# Project.net
KiCad netlist of a schematic drawn in EAGLE
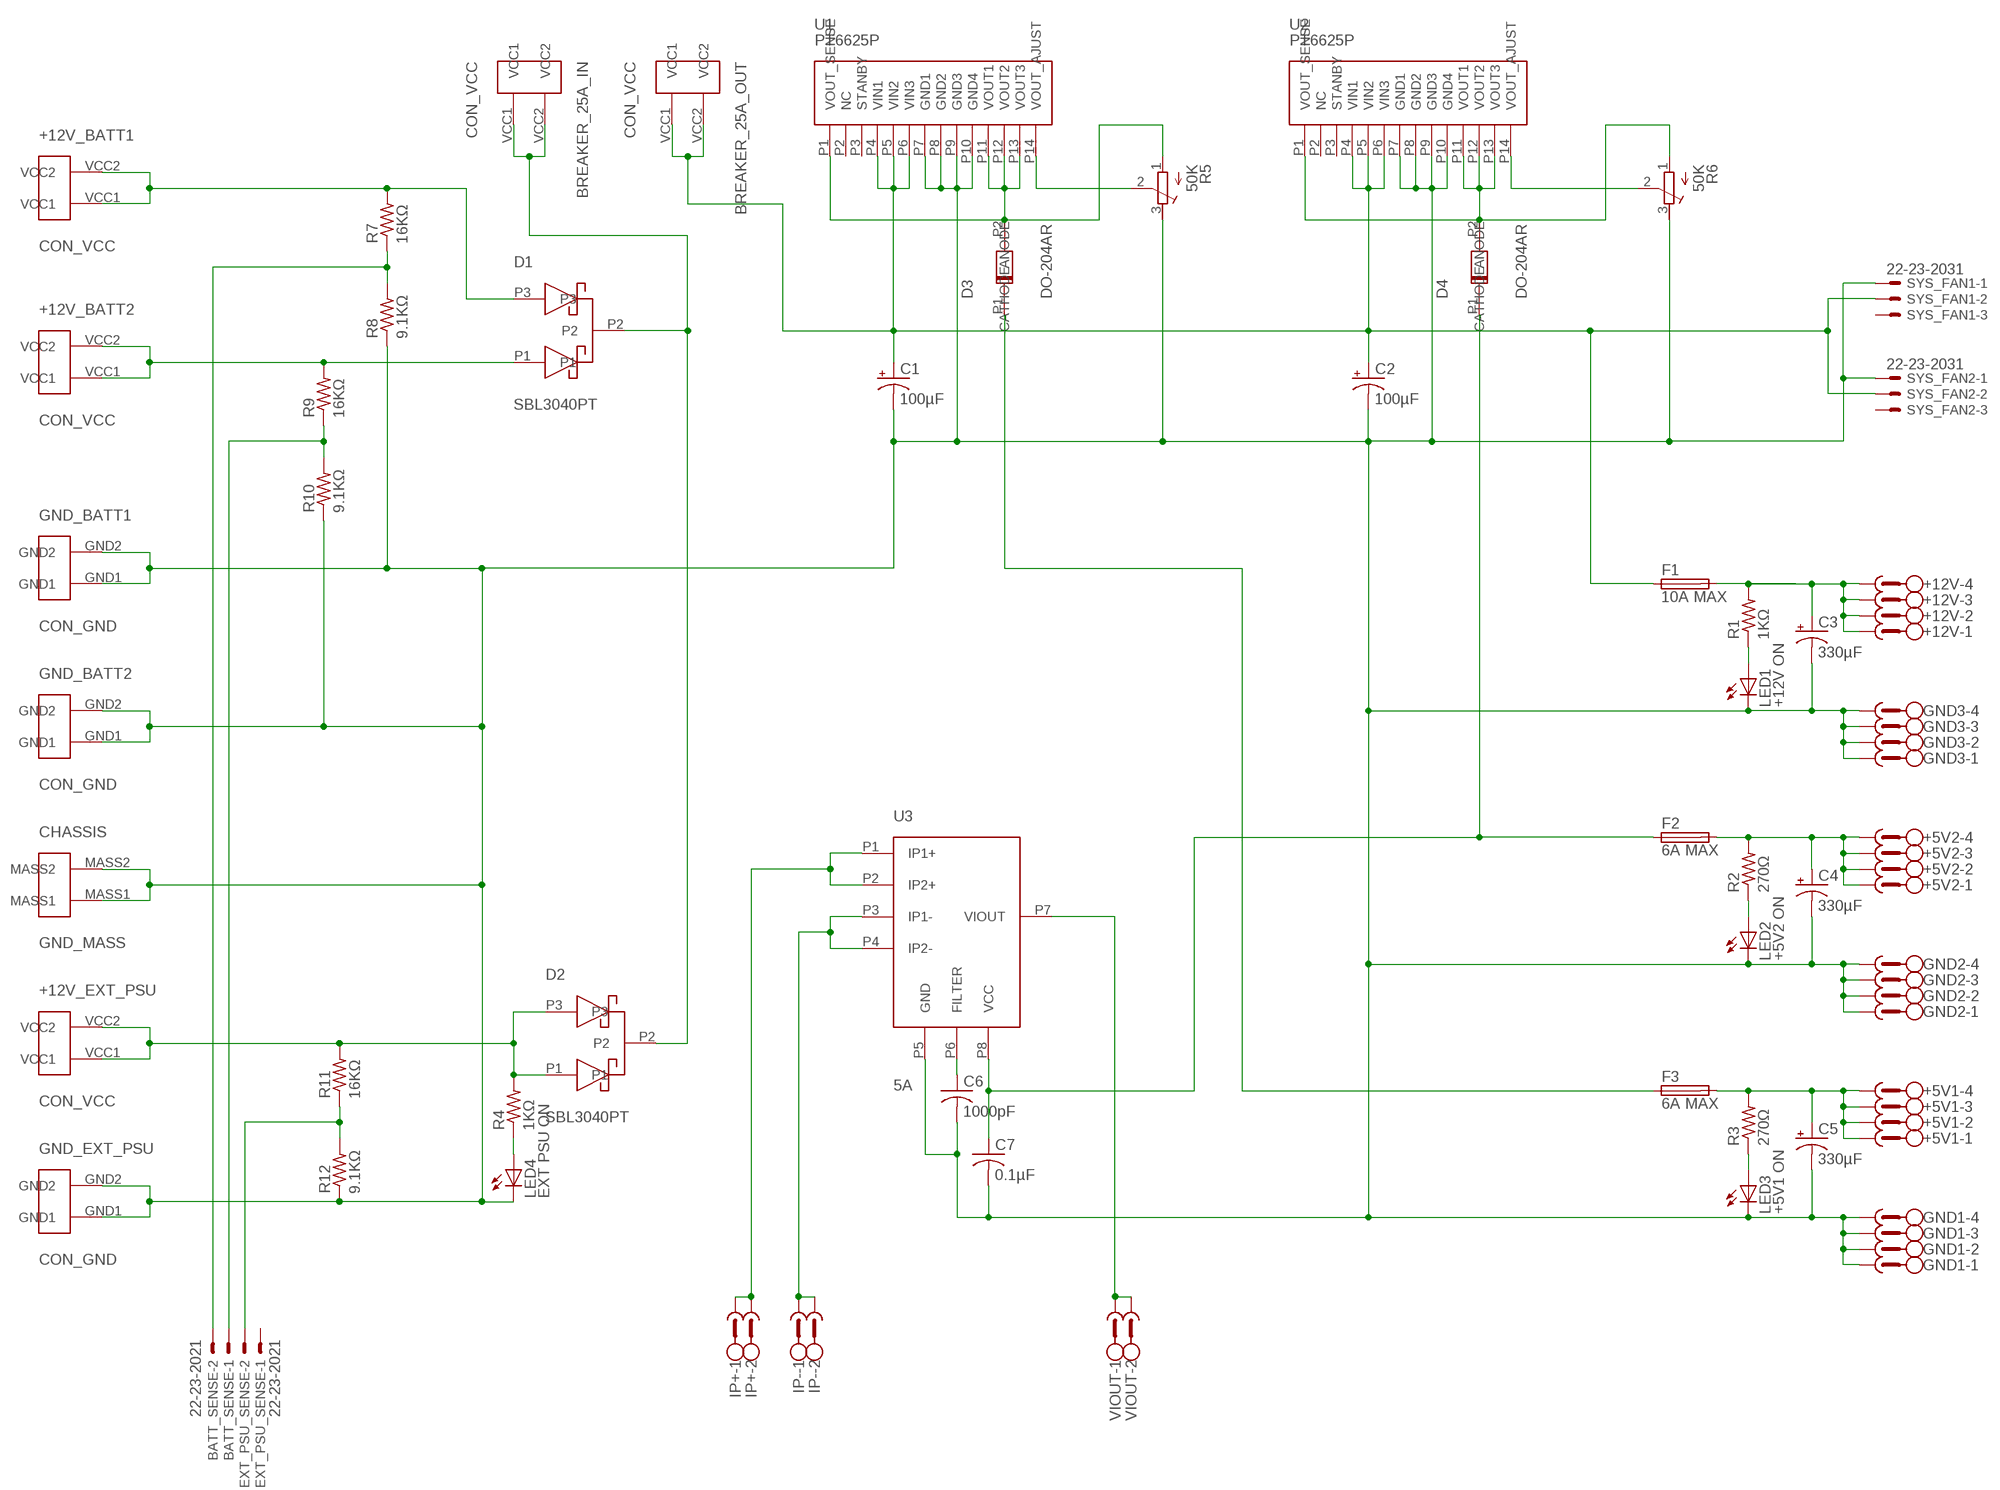
[diagram p0: schematic, sheet 1]

(export (version "E")
  (design (tool "Eeschema 10.0.6"))
  (components
    (comp (ref "+5V1")
      (value "MC1.5/4-G-3.81")
      (footprint "eagle-import:MC1.5_4-G-3.81")
      (libsource (lib "eagle-import") (part "MC1.5/4-G-3.81"))
    )
    (comp (ref "+5V2")
      (value "MC1.5/4-G-3.81")
      (footprint "eagle-import:MC1.5_4-G-3.81")
      (libsource (lib "eagle-import") (part "MC1.5/4-G-3.81"))
    )
    (comp (ref "+12V")
      (value "MC1.5/4-G-3.81")
      (footprint "eagle-import:MC1.5_4-G-3.81")
      (libsource (lib "eagle-import") (part "MC1.5/4-G-3.81"))
    )
    (comp (ref "+12V_BATT1")
      (value "CON_VCC")
      (footprint "eagle-import:CON_VCC")
      (libsource (lib "eagle-import") (part "CON_VCC"))
    )
    (comp (ref "+12V_BATT2")
      (value "CON_VCC")
      (footprint "eagle-import:CON_VCC")
      (libsource (lib "eagle-import") (part "CON_VCC"))
    )
    (comp (ref "+12V_EXT_PSU")
      (value "CON_VCC")
      (footprint "eagle-import:CON_VCC")
      (libsource (lib "eagle-import") (part "CON_VCC"))
    )
    (comp (ref "BATT_SENSE")
      (value "22-23-2021")
      (footprint "eagle-import:22-23-2021")
      (fields (field (name "MF") "MOLEX"))
      (libsource (lib "eagle-import") (part "22-23-2021"))
    )
    (comp (ref "BREAKER_25A_IN")
      (value "CON_VCC")
      (footprint "eagle-import:CON_VCC")
      (libsource (lib "eagle-import") (part "CON_VCC"))
    )
    (comp (ref "BREAKER_25A_OUT")
      (value "CON_VCC")
      (footprint "eagle-import:CON_VCC")
      (libsource (lib "eagle-import") (part "CON_VCC"))
    )
    (comp (ref "C1")
      (value "100µF")
      (footprint "eagle-import:E2,5-6")
      (libsource (lib "eagle-import") (part "CPOL-USE2.5-6"))
    )
    (comp (ref "C2")
      (value "100µF")
      (footprint "eagle-import:E2,5-6")
      (libsource (lib "eagle-import") (part "CPOL-USE2.5-6"))
    )
    (comp (ref "C3")
      (value "330µF")
      (footprint "eagle-import:E5-10,5")
      (libsource (lib "eagle-import") (part "CPOL-USE5-10.5"))
    )
    (comp (ref "C4")
      (value "330µF")
      (footprint "eagle-import:E5-10,5")
      (libsource (lib "eagle-import") (part "CPOL-USE5-10.5"))
    )
    (comp (ref "C5")
      (value "330µF")
      (footprint "eagle-import:E5-10,5")
      (libsource (lib "eagle-import") (part "CPOL-USE5-10.5"))
    )
    (comp (ref "C6")
      (value "1000pF")
      (footprint "eagle-import:C0805")
      (libsource (lib "eagle-import") (part "C-USC0805"))
    )
    (comp (ref "C7")
      (value "0.1µF")
      (footprint "eagle-import:C0805")
      (libsource (lib "eagle-import") (part "C-USC0805"))
    )
    (comp (ref "CHASSIS")
      (value "GND_MASS")
      (footprint "eagle-import:CON_MASS")
      (libsource (lib "eagle-import") (part "GND_MASS"))
    )
    (comp (ref "D1")
      (value "SBL3040PT")
      (footprint "eagle-import:SBL3040PT")
      (libsource (lib "eagle-import") (part "SBL3040PT"))
    )
    (comp (ref "D2")
      (value "SBL3040PT")
      (footprint "eagle-import:SBL3040PT")
      (libsource (lib "eagle-import") (part "SBL3040PT"))
    )
    (comp (ref "D3")
      (value "DO-204AR")
      (footprint "eagle-import:DO-204AR")
      (libsource (lib "eagle-import") (part "DO-204AR"))
    )
    (comp (ref "D4")
      (value "DO-204AR")
      (footprint "eagle-import:DO-204AR")
      (libsource (lib "eagle-import") (part "DO-204AR"))
    )
    (comp (ref "EXT_PSU_SENSE")
      (value "22-23-2021")
      (footprint "eagle-import:22-23-2021")
      (fields (field (name "MF") "MOLEX"))
      (libsource (lib "eagle-import") (part "22-23-2021"))
    )
    (comp (ref "F1")
      (value "10A MAX")
      (footprint "eagle-import:SH22,5")
      (fields (field (name "MF") "SCHURTER") (field (name "MPN") "0031.8201"))
      (libsource (lib "eagle-import") (part "SH22,5"))
    )
    (comp (ref "F2")
      (value "6A MAX")
      (footprint "eagle-import:SH22,5")
      (fields (field (name "MF") "SCHURTER") (field (name "MPN") "0031.8201"))
      (libsource (lib "eagle-import") (part "SH22,5"))
    )
    (comp (ref "F3")
      (value "6A MAX")
      (footprint "eagle-import:SH22,5")
      (fields (field (name "MF") "SCHURTER") (field (name "MPN") "0031.8201"))
      (libsource (lib "eagle-import") (part "SH22,5"))
    )
    (comp (ref "GND1")
      (value "MC1.5/4-G-3.81")
      (footprint "eagle-import:MC1.5_4-G-3.81")
      (libsource (lib "eagle-import") (part "MC1.5/4-G-3.81"))
    )
    (comp (ref "GND2")
      (value "MC1.5/4-G-3.81")
      (footprint "eagle-import:MC1.5_4-G-3.81")
      (libsource (lib "eagle-import") (part "MC1.5/4-G-3.81"))
    )
    (comp (ref "GND3")
      (value "MC1.5/4-G-3.81")
      (footprint "eagle-import:MC1.5_4-G-3.81")
      (libsource (lib "eagle-import") (part "MC1.5/4-G-3.81"))
    )
    (comp (ref "GND_BATT1")
      (value "CON_GND")
      (footprint "eagle-import:CON_GND")
      (libsource (lib "eagle-import") (part "CON_GND"))
    )
    (comp (ref "GND_BATT2")
      (value "CON_GND")
      (footprint "eagle-import:CON_GND")
      (libsource (lib "eagle-import") (part "CON_GND"))
    )
    (comp (ref "GND_EXT_PSU")
      (value "CON_GND")
      (footprint "eagle-import:CON_GND")
      (libsource (lib "eagle-import") (part "CON_GND"))
    )
    (comp (ref "IP+")
      (value "MC1.5/2-G-3.81")
      (footprint "eagle-import:MC1.5_2-G-3.81")
      (libsource (lib "eagle-import") (part "MC1.5/2-G-3.81"))
    )
    (comp (ref "IP-")
      (value "MC1.5/2-G-3.81")
      (footprint "eagle-import:MC1.5_2-G-3.81")
      (libsource (lib "eagle-import") (part "MC1.5/2-G-3.81"))
    )
    (comp (ref "LED1")
      (value "+12V ON")
      (footprint "eagle-import:CHIP-LED0805")
      (libsource (lib "eagle-import") (part "LEDCHIP-LED0805"))
    )
    (comp (ref "LED2")
      (value "+5V2 ON")
      (footprint "eagle-import:CHIP-LED0805")
      (libsource (lib "eagle-import") (part "LEDCHIP-LED0805"))
    )
    (comp (ref "LED3")
      (value "+5V1 ON")
      (footprint "eagle-import:CHIP-LED0805")
      (libsource (lib "eagle-import") (part "LEDCHIP-LED0805"))
    )
    (comp (ref "LED4")
      (value "EXT PSU ON")
      (footprint "eagle-import:CHIP-LED0805")
      (libsource (lib "eagle-import") (part "LEDCHIP-LED0805"))
    )
    (comp (ref "R1")
      (value "1KΩ")
      (footprint "eagle-import:M0805")
      (libsource (lib "eagle-import") (part "R-US_M0805"))
    )
    (comp (ref "R2")
      (value "270Ω")
      (footprint "eagle-import:M0805")
      (libsource (lib "eagle-import") (part "R-US_M0805"))
    )
    (comp (ref "R3")
      (value "270Ω")
      (footprint "eagle-import:M0805")
      (libsource (lib "eagle-import") (part "R-US_M0805"))
    )
    (comp (ref "R4")
      (value "1KΩ")
      (footprint "eagle-import:M0805")
      (libsource (lib "eagle-import") (part "R-US_M0805"))
    )
    (comp (ref "R5")
      (value "50K")
      (footprint "eagle-import:RTRIM3296Y")
      (libsource (lib "eagle-import") (part "R-TRIMM3296Y"))
    )
    (comp (ref "R6")
      (value "50K")
      (footprint "eagle-import:RTRIM3296Y")
      (libsource (lib "eagle-import") (part "R-TRIMM3296Y"))
    )
    (comp (ref "R7")
      (value "16KΩ")
      (footprint "eagle-import:R0805")
      (libsource (lib "eagle-import") (part "resistor_R-US_R0805"))
    )
    (comp (ref "R8")
      (value "9.1KΩ")
      (footprint "eagle-import:R0805")
      (libsource (lib "eagle-import") (part "resistor_R-US_R0805"))
    )
    (comp (ref "R9")
      (value "16KΩ")
      (footprint "eagle-import:R0805")
      (libsource (lib "eagle-import") (part "resistor_R-US_R0805"))
    )
    (comp (ref "R10")
      (value "9.1KΩ")
      (footprint "eagle-import:R0805")
      (libsource (lib "eagle-import") (part "resistor_R-US_R0805"))
    )
    (comp (ref "R11")
      (value "16KΩ")
      (footprint "eagle-import:R0805")
      (libsource (lib "eagle-import") (part "resistor_R-US_R0805"))
    )
    (comp (ref "R12")
      (value "9.1KΩ")
      (footprint "eagle-import:R0805")
      (libsource (lib "eagle-import") (part "resistor_R-US_R0805"))
    )
    (comp (ref "SYS_FAN1")
      (value "22-23-2031")
      (footprint "eagle-import:22-23-2031")
      (fields (field (name "MF") "MOLEX"))
      (libsource (lib "eagle-import") (part "22-23-2031"))
    )
    (comp (ref "SYS_FAN2")
      (value "22-23-2031")
      (footprint "eagle-import:22-23-2031")
      (fields (field (name "MF") "MOLEX"))
      (libsource (lib "eagle-import") (part "22-23-2031"))
    )
    (comp (ref "U1")
      (value "PT6625P")
      (footprint "eagle-import:PT6625P")
      (libsource (lib "eagle-import") (part "PT6625P"))
    )
    (comp (ref "U2")
      (value "PT6625P")
      (footprint "eagle-import:PT6625P")
      (libsource (lib "eagle-import") (part "PT6625P"))
    )
    (comp (ref "U3")
      (value "5A")
      (footprint "eagle-import:ACS712")
      (libsource (lib "eagle-import") (part "ACS712"))
    )
    (comp (ref "VIOUT")
      (value "MC1.5/2-G-3.81")
      (footprint "eagle-import:MC1.5_2-G-3.81")
      (libsource (lib "eagle-import") (part "MC1.5/2-G-3.81"))
    )
  )
  (nets
    (net (code "1") (name "Net-(+5V1B-1)") (class "Default")
      (node (ref "+5V1") (pin "1") (pinfunction "1_1") (pintype "passive"))
      (node (ref "+5V1") (pin "2") (pinfunction "1_2") (pintype "passive"))
      (node (ref "+5V1") (pin "3") (pinfunction "1_3") (pintype "passive"))
      (node (ref "+5V1") (pin "4") (pinfunction "1_4") (pintype "passive"))
      (node (ref "C5") (pin "+") (pinfunction "+_+") (pintype "passive"))
      (node (ref "F3") (pin "2") (pinfunction "2_2") (pintype "passive"))
      (node (ref "R3") (pin "2") (pinfunction "2_2") (pintype "passive"))
    )
    (net (code "2") (name "Net-(+5V2B-1)") (class "Default")
      (node (ref "+5V2") (pin "1") (pinfunction "1_1") (pintype "passive"))
      (node (ref "+5V2") (pin "2") (pinfunction "1_2") (pintype "passive"))
      (node (ref "+5V2") (pin "3") (pinfunction "1_3") (pintype "passive"))
      (node (ref "+5V2") (pin "4") (pinfunction "1_4") (pintype "passive"))
      (node (ref "C4") (pin "+") (pinfunction "+_+") (pintype "passive"))
      (node (ref "F2") (pin "2") (pinfunction "2_2") (pintype "passive"))
      (node (ref "R2") (pin "2") (pinfunction "2_2") (pintype "passive"))
    )
    (net (code "3") (name "Net-(+12VB-1)") (class "Default")
      (node (ref "+12V") (pin "1") (pinfunction "1_1") (pintype "passive"))
      (node (ref "+12V") (pin "2") (pinfunction "1_2") (pintype "passive"))
      (node (ref "+12V") (pin "3") (pinfunction "1_3") (pintype "passive"))
      (node (ref "+12V") (pin "4") (pinfunction "1_4") (pintype "passive"))
      (node (ref "C3") (pin "+") (pinfunction "+_+") (pintype "passive"))
      (node (ref "F1") (pin "2") (pinfunction "2_2") (pintype "passive"))
      (node (ref "R1") (pin "2") (pinfunction "2_2") (pintype "passive"))
    )
    (net (code "4") (name "Net-(+12V_BATT1-PadVCC1)") (class "Default")
      (node (ref "+12V_BATT1") (pin "VCC1") (pinfunction "VCC1_VCC1") (pintype "power_in"))
      (node (ref "+12V_BATT1") (pin "VCC2") (pinfunction "VCC2_VCC2") (pintype "power_in"))
      (node (ref "D1") (pin "P3") (pinfunction "P3_P3") (pintype "passive"))
      (node (ref "R7") (pin "2") (pinfunction "2_2") (pintype "passive"))
    )
    (net (code "5") (name "Net-(+12V_BATT2-PadVCC1)") (class "Default")
      (node (ref "+12V_BATT2") (pin "VCC1") (pinfunction "VCC1_VCC1") (pintype "power_in"))
      (node (ref "+12V_BATT2") (pin "VCC2") (pinfunction "VCC2_VCC2") (pintype "power_in"))
      (node (ref "D1") (pin "P1") (pinfunction "P1_P1") (pintype "passive"))
      (node (ref "R9") (pin "2") (pinfunction "2_2") (pintype "passive"))
    )
    (net (code "6") (name "Net-(+12V_EXT_PSU-PadVCC1)") (class "Default")
      (node (ref "+12V_EXT_PSU") (pin "VCC1") (pinfunction "VCC1_VCC1") (pintype "power_in"))
      (node (ref "+12V_EXT_PSU") (pin "VCC2") (pinfunction "VCC2_VCC2") (pintype "power_in"))
      (node (ref "D2") (pin "P1") (pinfunction "P1_P1") (pintype "passive"))
      (node (ref "D2") (pin "P3") (pinfunction "P3_P3") (pintype "passive"))
      (node (ref "R11") (pin "2") (pinfunction "2_2") (pintype "passive"))
      (node (ref "R4") (pin "2") (pinfunction "2_2") (pintype "passive"))
    )
    (net (code "7") (name "Net-(BATT_SENSEA-S)") (class "Default")
      (node (ref "BATT_SENSE") (pin "1") (pinfunction "S_1") (pintype "passive"))
      (node (ref "R10") (pin "2") (pinfunction "2_2") (pintype "passive"))
      (node (ref "R9") (pin "1") (pinfunction "1_1") (pintype "passive"))
    )
    (net (code "8") (name "Net-(BATT_SENSEB-S)") (class "Default")
      (node (ref "BATT_SENSE") (pin "2") (pinfunction "S_2") (pintype "passive"))
      (node (ref "R7") (pin "1") (pinfunction "1_1") (pintype "passive"))
      (node (ref "R8") (pin "2") (pinfunction "2_2") (pintype "passive"))
    )
    (net (code "9") (name "Net-(BREAKER_25A_IN-PadVCC1)") (class "Default")
      (node (ref "BREAKER_25A_IN") (pin "VCC1") (pinfunction "VCC1_VCC1") (pintype "power_in"))
      (node (ref "BREAKER_25A_IN") (pin "VCC2") (pinfunction "VCC2_VCC2") (pintype "power_in"))
      (node (ref "D1") (pin "P2") (pinfunction "P2_P2") (pintype "passive"))
      (node (ref "D2") (pin "P2") (pinfunction "P2_P2") (pintype "passive"))
    )
    (net (code "10") (name "Net-(D3-ANODE)") (class "Default")
      (node (ref "D3") (pin "P1") (pinfunction "ANODE_P1") (pintype "passive"))
      (node (ref "F3") (pin "1") (pinfunction "1_1") (pintype "passive"))
    )
    (net (code "11") (name "Net-(D3-CATHODE)") (class "Default")
      (node (ref "D3") (pin "P2") (pinfunction "CATHODE_P2") (pintype "passive"))
      (node (ref "R5") (pin "1") (pinfunction "E_1") (pintype "passive"))
      (node (ref "U1") (pin "P1") (pinfunction "VOUT_SENSE_P1") (pintype "bidirectional"))
      (node (ref "U1") (pin "P11") (pinfunction "VOUT1_P11") (pintype "bidirectional"))
      (node (ref "U1") (pin "P12") (pinfunction "VOUT2_P12") (pintype "bidirectional"))
      (node (ref "U1") (pin "P13") (pinfunction "VOUT3_P13") (pintype "bidirectional"))
    )
    (net (code "12") (name "Net-(D4-ANODE)") (class "Default")
      (node (ref "C7") (pin "1") (pinfunction "1_1") (pintype "passive"))
      (node (ref "D4") (pin "P1") (pinfunction "ANODE_P1") (pintype "passive"))
      (node (ref "F2") (pin "1") (pinfunction "1_1") (pintype "passive"))
      (node (ref "U3") (pin "P8") (pinfunction "VCC_P8") (pintype "power_in"))
    )
    (net (code "13") (name "Net-(D4-CATHODE)") (class "Default")
      (node (ref "D4") (pin "P2") (pinfunction "CATHODE_P2") (pintype "passive"))
      (node (ref "R6") (pin "1") (pinfunction "E_1") (pintype "passive"))
      (node (ref "U2") (pin "P1") (pinfunction "VOUT_SENSE_P1") (pintype "bidirectional"))
      (node (ref "U2") (pin "P11") (pinfunction "VOUT1_P11") (pintype "bidirectional"))
      (node (ref "U2") (pin "P12") (pinfunction "VOUT2_P12") (pintype "bidirectional"))
      (node (ref "U2") (pin "P13") (pinfunction "VOUT3_P13") (pintype "bidirectional"))
    )
    (net (code "14") (name "Net-(EXT_PSU_SENSEB-S)") (class "Default")
      (node (ref "EXT_PSU_SENSE") (pin "2") (pinfunction "S_2") (pintype "passive"))
      (node (ref "R11") (pin "1") (pinfunction "1_1") (pintype "passive"))
      (node (ref "R12") (pin "2") (pinfunction "2_2") (pintype "passive"))
    )
    (net (code "15") (name "Net-(GND1B-1)") (class "Default")
      (node (ref "C1") (pin "-") (pinfunction "-_-") (pintype "passive"))
      (node (ref "C2") (pin "-") (pinfunction "-_-") (pintype "passive"))
      (node (ref "C3") (pin "-") (pinfunction "-_-") (pintype "passive"))
      (node (ref "C4") (pin "-") (pinfunction "-_-") (pintype "passive"))
      (node (ref "C5") (pin "-") (pinfunction "-_-") (pintype "passive"))
      (node (ref "C6") (pin "2") (pinfunction "2_2") (pintype "passive"))
      (node (ref "C7") (pin "2") (pinfunction "2_2") (pintype "passive"))
      (node (ref "CHASSIS") (pin "MASS1") (pinfunction "MASS1_MASS1") (pintype "power_in"))
      (node (ref "CHASSIS") (pin "MASS2") (pinfunction "MASS2_MASS2") (pintype "power_in"))
      (node (ref "GND1") (pin "1") (pinfunction "1_1") (pintype "passive"))
      (node (ref "GND1") (pin "2") (pinfunction "1_2") (pintype "passive"))
      (node (ref "GND1") (pin "3") (pinfunction "1_3") (pintype "passive"))
      (node (ref "GND1") (pin "4") (pinfunction "1_4") (pintype "passive"))
      (node (ref "GND2") (pin "1") (pinfunction "1_1") (pintype "passive"))
      (node (ref "GND2") (pin "2") (pinfunction "1_2") (pintype "passive"))
      (node (ref "GND2") (pin "3") (pinfunction "1_3") (pintype "passive"))
      (node (ref "GND2") (pin "4") (pinfunction "1_4") (pintype "passive"))
      (node (ref "GND3") (pin "1") (pinfunction "1_1") (pintype "passive"))
      (node (ref "GND3") (pin "2") (pinfunction "1_2") (pintype "passive"))
      (node (ref "GND3") (pin "3") (pinfunction "1_3") (pintype "passive"))
      (node (ref "GND3") (pin "4") (pinfunction "1_4") (pintype "passive"))
      (node (ref "GND_BATT1") (pin "GND1") (pinfunction "GND1_GND1") (pintype "power_in"))
      (node (ref "GND_BATT1") (pin "GND2") (pinfunction "GND2_GND2") (pintype "power_in"))
      (node (ref "GND_BATT2") (pin "GND1") (pinfunction "GND1_GND1") (pintype "power_in"))
      (node (ref "GND_BATT2") (pin "GND2") (pinfunction "GND2_GND2") (pintype "power_in"))
      (node (ref "GND_EXT_PSU") (pin "GND1") (pinfunction "GND1_GND1") (pintype "power_in"))
      (node (ref "GND_EXT_PSU") (pin "GND2") (pinfunction "GND2_GND2") (pintype "power_in"))
      (node (ref "LED1") (pin "C") (pinfunction "C_C") (pintype "passive"))
      (node (ref "LED2") (pin "C") (pinfunction "C_C") (pintype "passive"))
      (node (ref "LED3") (pin "C") (pinfunction "C_C") (pintype "passive"))
      (node (ref "LED4") (pin "C") (pinfunction "C_C") (pintype "passive"))
      (node (ref "R10") (pin "1") (pinfunction "1_1") (pintype "passive"))
      (node (ref "R12") (pin "1") (pinfunction "1_1") (pintype "passive"))
      (node (ref "R5") (pin "3") (pinfunction "A_3") (pintype "passive"))
      (node (ref "R6") (pin "3") (pinfunction "A_3") (pintype "passive"))
      (node (ref "R8") (pin "1") (pinfunction "1_1") (pintype "passive"))
      (node (ref "SYS_FAN1") (pin "1") (pinfunction "S_1") (pintype "passive"))
      (node (ref "SYS_FAN2") (pin "1") (pinfunction "S_1") (pintype "passive"))
      (node (ref "U1") (pin "P10") (pinfunction "GND4_P10") (pintype "power_in"))
      (node (ref "U1") (pin "P7") (pinfunction "GND1_P7") (pintype "power_in"))
      (node (ref "U1") (pin "P8") (pinfunction "GND2_P8") (pintype "power_in"))
      (node (ref "U1") (pin "P9") (pinfunction "GND3_P9") (pintype "power_in"))
      (node (ref "U2") (pin "P10") (pinfunction "GND4_P10") (pintype "power_in"))
      (node (ref "U2") (pin "P7") (pinfunction "GND1_P7") (pintype "power_in"))
      (node (ref "U2") (pin "P8") (pinfunction "GND2_P8") (pintype "power_in"))
      (node (ref "U2") (pin "P9") (pinfunction "GND3_P9") (pintype "power_in"))
      (node (ref "U3") (pin "P5") (pinfunction "GND_P5") (pintype "power_in"))
    )
    (net (code "16") (name "Net-(IP+B-1)") (class "Default")
      (node (ref "IP+") (pin "1") (pinfunction "1_1") (pintype "passive"))
      (node (ref "IP+") (pin "2") (pinfunction "1_2") (pintype "passive"))
      (node (ref "U3") (pin "P1") (pinfunction "IP1+_P1") (pintype "input"))
      (node (ref "U3") (pin "P2") (pinfunction "IP2+_P2") (pintype "input"))
    )
    (net (code "17") (name "Net-(IP-B-1)") (class "Default")
      (node (ref "IP-") (pin "1") (pinfunction "1_1") (pintype "passive"))
      (node (ref "IP-") (pin "2") (pinfunction "1_2") (pintype "passive"))
      (node (ref "U3") (pin "P3") (pinfunction "IP1-_P3") (pintype "input"))
      (node (ref "U3") (pin "P4") (pinfunction "IP2-_P4") (pintype "input"))
    )
    (net (code "18") (name "Net-(LED1-PadA)") (class "Default")
      (node (ref "LED1") (pin "A") (pinfunction "A_A") (pintype "passive"))
      (node (ref "R1") (pin "1") (pinfunction "1_1") (pintype "passive"))
    )
    (net (code "19") (name "Net-(LED2-PadA)") (class "Default")
      (node (ref "LED2") (pin "A") (pinfunction "A_A") (pintype "passive"))
      (node (ref "R2") (pin "1") (pinfunction "1_1") (pintype "passive"))
    )
    (net (code "20") (name "Net-(LED3-PadA)") (class "Default")
      (node (ref "LED3") (pin "A") (pinfunction "A_A") (pintype "passive"))
      (node (ref "R3") (pin "1") (pinfunction "1_1") (pintype "passive"))
    )
    (net (code "21") (name "Net-(LED4-PadA)") (class "Default")
      (node (ref "LED4") (pin "A") (pinfunction "A_A") (pintype "passive"))
      (node (ref "R4") (pin "1") (pinfunction "1_1") (pintype "passive"))
    )
    (net (code "22") (name "Net-(R5-S)") (class "Default")
      (node (ref "R5") (pin "2") (pinfunction "S_2") (pintype "passive"))
      (node (ref "U1") (pin "P14") (pinfunction "VOUT_AJUST_P14") (pintype "bidirectional"))
    )
    (net (code "23") (name "Net-(R6-S)") (class "Default")
      (node (ref "R6") (pin "2") (pinfunction "S_2") (pintype "passive"))
      (node (ref "U2") (pin "P14") (pinfunction "VOUT_AJUST_P14") (pintype "bidirectional"))
    )
    (net (code "24") (name "Net-(SYS_FAN1B-S)") (class "Default")
      (node (ref "BREAKER_25A_OUT") (pin "VCC1") (pinfunction "VCC1_VCC1") (pintype "power_in"))
      (node (ref "BREAKER_25A_OUT") (pin "VCC2") (pinfunction "VCC2_VCC2") (pintype "power_in"))
      (node (ref "C1") (pin "+") (pinfunction "+_+") (pintype "passive"))
      (node (ref "C2") (pin "+") (pinfunction "+_+") (pintype "passive"))
      (node (ref "F1") (pin "1") (pinfunction "1_1") (pintype "passive"))
      (node (ref "SYS_FAN1") (pin "2") (pinfunction "S_2") (pintype "passive"))
      (node (ref "SYS_FAN2") (pin "2") (pinfunction "S_2") (pintype "passive"))
      (node (ref "U1") (pin "P4") (pinfunction "VIN1_P4") (pintype "power_in"))
      (node (ref "U1") (pin "P5") (pinfunction "VIN2_P5") (pintype "power_in"))
      (node (ref "U1") (pin "P6") (pinfunction "VIN3_P6") (pintype "power_in"))
      (node (ref "U2") (pin "P4") (pinfunction "VIN1_P4") (pintype "power_in"))
      (node (ref "U2") (pin "P5") (pinfunction "VIN2_P5") (pintype "power_in"))
      (node (ref "U2") (pin "P6") (pinfunction "VIN3_P6") (pintype "power_in"))
    )
    (net (code "25") (name "Net-(U3-FILTER)") (class "Default")
      (node (ref "C6") (pin "1") (pinfunction "1_1") (pintype "passive"))
      (node (ref "U3") (pin "P6") (pinfunction "FILTER_P6") (pintype "bidirectional"))
    )
    (net (code "26") (name "Net-(U3-VIOUT)") (class "Default")
      (node (ref "U3") (pin "P7") (pinfunction "VIOUT_P7") (pintype "output"))
      (node (ref "VIOUT") (pin "1") (pinfunction "1_1") (pintype "passive"))
      (node (ref "VIOUT") (pin "2") (pinfunction "1_2") (pintype "passive"))
    )
    (net (code "27") (name "unconnected-(EXT_PSU_SENSEA-S-Pad1)") (class "Default")
      (node (ref "EXT_PSU_SENSE") (pin "1") (pinfunction "S_1") (pintype "passive"))
    )
    (net (code "28") (name "unconnected-(SYS_FAN1C-S-Pad3)") (class "Default")
      (node (ref "SYS_FAN1") (pin "3") (pinfunction "S_3") (pintype "passive"))
    )
    (net (code "29") (name "unconnected-(SYS_FAN2C-S-Pad3)") (class "Default")
      (node (ref "SYS_FAN2") (pin "3") (pinfunction "S_3") (pintype "passive"))
    )
    (net (code "30") (name "unconnected-(U1-NC-PadP2)") (class "Default")
      (node (ref "U1") (pin "P2") (pinfunction "NC_P2") (pintype "no_connect"))
    )
    (net (code "31") (name "unconnected-(U1-STANBY-PadP3)") (class "Default")
      (node (ref "U1") (pin "P3") (pinfunction "STANBY_P3") (pintype "no_connect"))
    )
    (net (code "32") (name "unconnected-(U2-NC-PadP2)") (class "Default")
      (node (ref "U2") (pin "P2") (pinfunction "NC_P2") (pintype "no_connect"))
    )
    (net (code "33") (name "unconnected-(U2-STANBY-PadP3)") (class "Default")
      (node (ref "U2") (pin "P3") (pinfunction "STANBY_P3") (pintype "no_connect"))
    )
  )
)
